# Iso_Current_Limit.net
KiCad netlist of a schematic drawn in Altium Designer
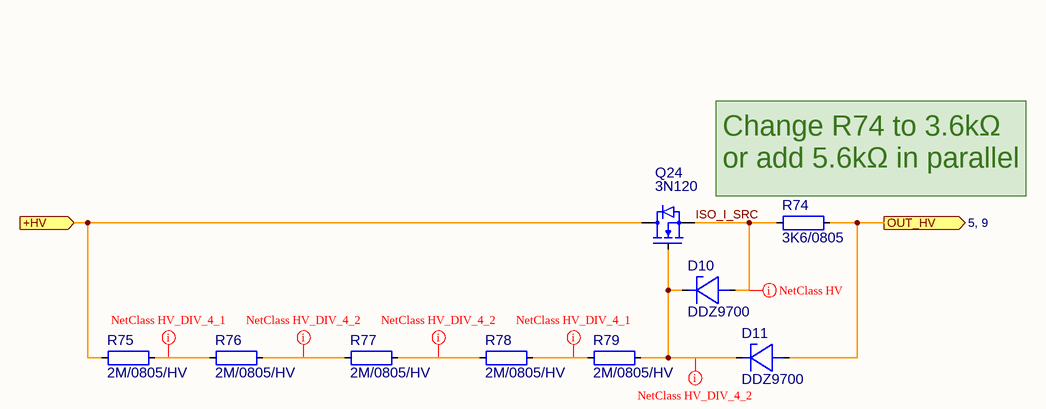
[diagram p0: Iso_Current_Limit.SchDoc]

(export (version "E")
  (design (tool "Eeschema 10.0.6"))
  (components
    (comp (ref "D10")
      (value "DDZ9700")
      (footprint "SOD3718X125")
      (description "Low current zener diode 13V 500mW SOD123")
      (fields (field (name "MANUFACTURER") "Diodes Incorporated"))
      (libsource (lib "daniw_altium_lib") (part "D_Zener"))
    )
    (comp (ref "D11")
      (value "DDZ9700")
      (footprint "SOD3718X125")
      (description "Low current zener diode 13V 500mW SOD123")
      (fields (field (name "MANUFACTURER") "Diodes Incorporated"))
      (libsource (lib "daniw_altium_lib") (part "D_Zener"))
    )
    (comp (ref "Q24")
      (value "3N120")
      (footprint "TO228P990X229-3")
      (description "N-Channel MOSFET 1200V")
      (fields (field (name "MANUFACTURER") "Tech Public"))
      (libsource (lib "daniw_altium_lib") (part "MOSFET_N_G1_D3_S2"))
    )
    (comp (ref "R74")
      (value "3K6/0805")
      (footprint "R0805-0.50-WW")
      (description "RES SM 0805 3K6")
      (fields (field (name "MANUFACTURER") "GENERIC"))
      (libsource (lib "daniw_altium_lib") (part "R"))
    )
    (comp (ref "R75")
      (value "2M/0805/HV")
      (footprint "R0805-0.50-HV-WW")
      (description "RES SM 0805 2M High voltage")
      (fields (field (name "MANUFACTURER") "GENERIC"))
      (libsource (lib "daniw_altium_lib") (part "R"))
    )
    (comp (ref "R76")
      (value "2M/0805/HV")
      (footprint "R0805-0.50-HV-WW")
      (description "RES SM 0805 2M High voltage")
      (fields (field (name "MANUFACTURER") "GENERIC"))
      (libsource (lib "daniw_altium_lib") (part "R"))
    )
    (comp (ref "R77")
      (value "2M/0805/HV")
      (footprint "R0805-0.50-HV-WW")
      (description "RES SM 0805 2M High voltage")
      (fields (field (name "MANUFACTURER") "GENERIC"))
      (libsource (lib "daniw_altium_lib") (part "R"))
    )
    (comp (ref "R78")
      (value "2M/0805/HV")
      (footprint "R0805-0.50-HV-WW")
      (description "RES SM 0805 2M High voltage")
      (fields (field (name "MANUFACTURER") "GENERIC"))
      (libsource (lib "daniw_altium_lib") (part "R"))
    )
    (comp (ref "R79")
      (value "2M/0805/HV")
      (footprint "R0805-0.50-HV-WW")
      (description "RES SM 0805 2M High voltage")
      (fields (field (name "MANUFACTURER") "GENERIC"))
      (libsource (lib "daniw_altium_lib") (part "R"))
    )
  )
  (nets
    (net (code "1") (name "/+HV") (class "Default")
      (node (ref "Q24") (pin "3") (pinfunction "DRAIN_3") (pintype "passive"))
      (node (ref "R75") (pin "2") (pinfunction "2_2") (pintype "passive"))
    )
    (net (code "2") (name "/ISO_I_SRC") (class "Default")
      (node (ref "D10") (pin "2") (pinfunction "A_2") (pintype "passive"))
      (node (ref "Q24") (pin "2") (pinfunction "SOURCE_2") (pintype "passive"))
      (node (ref "R74") (pin "1") (pinfunction "1_1") (pintype "passive"))
    )
    (net (code "3") (name "/OUT_HV") (class "Default")
      (node (ref "D11") (pin "2") (pinfunction "A_2") (pintype "passive"))
      (node (ref "R74") (pin "2") (pinfunction "2_2") (pintype "passive"))
    )
    (net (code "4") (name "Net-(D10-C)") (class "Default")
      (node (ref "D10") (pin "1") (pinfunction "C_1") (pintype "passive"))
      (node (ref "D11") (pin "1") (pinfunction "C_1") (pintype "passive"))
      (node (ref "Q24") (pin "1") (pinfunction "GATE_1") (pintype "passive"))
      (node (ref "R79") (pin "2") (pinfunction "2_2") (pintype "passive"))
    )
    (net (code "5") (name "Net-(R75-Pad1)") (class "Default")
      (node (ref "R75") (pin "1") (pinfunction "1_1") (pintype "passive"))
      (node (ref "R76") (pin "2") (pinfunction "2_2") (pintype "passive"))
    )
    (net (code "6") (name "Net-(R76-Pad1)") (class "Default")
      (node (ref "R76") (pin "1") (pinfunction "1_1") (pintype "passive"))
      (node (ref "R77") (pin "2") (pinfunction "2_2") (pintype "passive"))
    )
    (net (code "7") (name "Net-(R77-Pad1)") (class "Default")
      (node (ref "R77") (pin "1") (pinfunction "1_1") (pintype "passive"))
      (node (ref "R78") (pin "2") (pinfunction "2_2") (pintype "passive"))
    )
    (net (code "8") (name "Net-(R78-Pad1)") (class "Default")
      (node (ref "R78") (pin "1") (pinfunction "1_1") (pintype "passive"))
      (node (ref "R79") (pin "1") (pinfunction "1_1") (pintype "passive"))
    )
  )
)
